# LED_Test.net
KiCad netlist of a schematic drawn in EAGLE
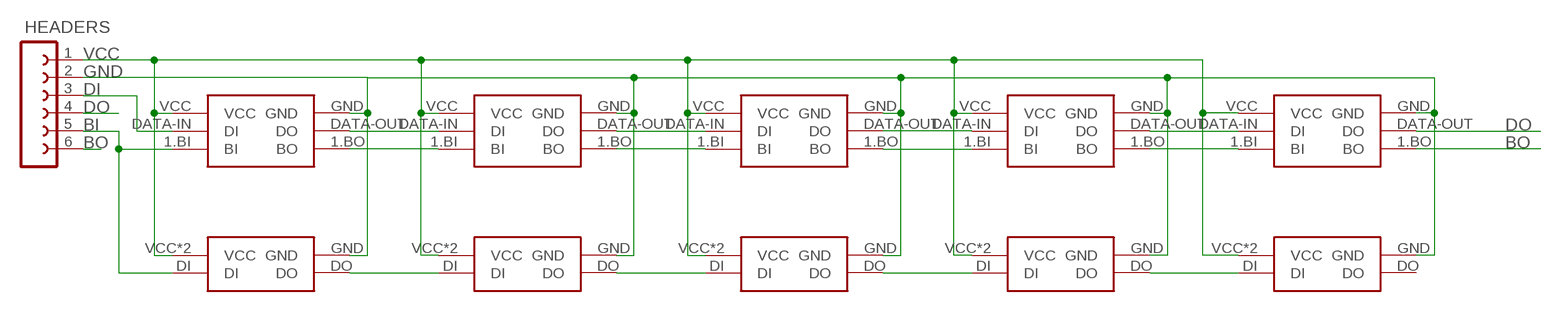
[diagram p0: schematic, sheet 1]

(export (version "E")
  (design (tool "Eeschema 10.0.6"))
  (components
    (comp (ref "HEADERS")
      (value "FE06-1")
      (footprint "eagle-import:FE06")
      (libsource (lib "eagle-import") (part "FE06-1"))
    )
    (comp (ref "U$1")
      (value "OPTO-PIXEL.COMBINEDCOMBINED-V1.04")
      (footprint "eagle-import:COMBINED4")
      (libsource (lib "eagle-import") (part "OPTO-PIXEL.COMBINEDCOMBINED-V1.04"))
    )
    (comp (ref "U$2")
      (value "OPTO-PIXEL.COMBINEDCOMBINED-V1.04")
      (footprint "eagle-import:COMBINED4")
      (libsource (lib "eagle-import") (part "OPTO-PIXEL.COMBINEDCOMBINED-V1.04"))
    )
    (comp (ref "U$3")
      (value "OPTO-PIXEL.COMBINEDCOMBINED-V1.04")
      (footprint "eagle-import:COMBINED4")
      (libsource (lib "eagle-import") (part "OPTO-PIXEL.COMBINEDCOMBINED-V1.04"))
    )
    (comp (ref "U$4")
      (value "OPTO-PIXEL.COMBINEDCOMBINED-V1.04")
      (footprint "eagle-import:COMBINED4")
      (libsource (lib "eagle-import") (part "OPTO-PIXEL.COMBINEDCOMBINED-V1.04"))
    )
    (comp (ref "U$5")
      (value "OPTO-PIXEL.COMBINEDCOMBINED-V1.04")
      (footprint "eagle-import:COMBINED4")
      (libsource (lib "eagle-import") (part "OPTO-PIXEL.COMBINEDCOMBINED-V1.04"))
    )
    (comp (ref "U$6")
      (value "OPTO-PIXEL.IN-PI55TBTPRPGPBIN-PI55TBTPRPGPB")
      (footprint "eagle-import:IN-PI55TBTPRPGPB")
      (libsource (lib "eagle-import") (part "OPTO-PIXEL.IN-PI55TBTPRPGPBIN-PI55TBTPRPGPB"))
    )
    (comp (ref "U$7")
      (value "OPTO-PIXEL.IN-PI55TBTPRPGPBIN-PI55TBTPRPGPB")
      (footprint "eagle-import:IN-PI55TBTPRPGPB")
      (libsource (lib "eagle-import") (part "OPTO-PIXEL.IN-PI55TBTPRPGPBIN-PI55TBTPRPGPB"))
    )
    (comp (ref "U$8")
      (value "OPTO-PIXEL.IN-PI55TBTPRPGPBIN-PI55TBTPRPGPB")
      (footprint "eagle-import:IN-PI55TBTPRPGPB")
      (libsource (lib "eagle-import") (part "OPTO-PIXEL.IN-PI55TBTPRPGPBIN-PI55TBTPRPGPB"))
    )
    (comp (ref "U$9")
      (value "OPTO-PIXEL.IN-PI55TBTPRPGPBIN-PI55TBTPRPGPB")
      (footprint "eagle-import:IN-PI55TBTPRPGPB")
      (libsource (lib "eagle-import") (part "OPTO-PIXEL.IN-PI55TBTPRPGPBIN-PI55TBTPRPGPB"))
    )
    (comp (ref "U$10")
      (value "OPTO-PIXEL.IN-PI55TBTPRPGPBIN-PI55TBTPRPGPB")
      (footprint "eagle-import:IN-PI55TBTPRPGPB")
      (libsource (lib "eagle-import") (part "OPTO-PIXEL.IN-PI55TBTPRPGPBIN-PI55TBTPRPGPB"))
    )
  )
  (nets
    (net (code "1") (name "/BI") (class "Default")
      (node (ref "HEADERS") (pin "5") (pinfunction "5_5") (pintype "passive"))
      (node (ref "U$1") (pin "1.BI") (pinfunction "BI_1.BI") (pintype "bidirectional"))
      (node (ref "U$6") (pin "DI") (pinfunction "DI_DI") (pintype "bidirectional"))
    )
    (net (code "2") (name "/BO") (class "Default")
      (node (ref "HEADERS") (pin "6") (pinfunction "6_6") (pintype "passive"))
      (node (ref "U$5") (pin "1.BO") (pinfunction "BO_1.BO") (pintype "bidirectional"))
    )
    (net (code "3") (name "/DI") (class "Default")
      (node (ref "HEADERS") (pin "3") (pinfunction "3_3") (pintype "passive"))
      (node (ref "U$1") (pin "DATA-IN") (pinfunction "DI_DATA-IN") (pintype "bidirectional"))
    )
    (net (code "4") (name "/DO") (class "Default")
      (node (ref "HEADERS") (pin "4") (pinfunction "4_4") (pintype "passive"))
      (node (ref "U$5") (pin "DATA-OUT") (pinfunction "DO_DATA-OUT") (pintype "bidirectional"))
    )
    (net (code "5") (name "/GND") (class "Default")
      (node (ref "HEADERS") (pin "2") (pinfunction "2_2") (pintype "passive"))
      (node (ref "U$1") (pin "GND") (pinfunction "GND_GND") (pintype "bidirectional"))
      (node (ref "U$10") (pin "GND") (pinfunction "GND_GND") (pintype "bidirectional"))
      (node (ref "U$2") (pin "GND") (pinfunction "GND_GND") (pintype "bidirectional"))
      (node (ref "U$3") (pin "GND") (pinfunction "GND_GND") (pintype "bidirectional"))
      (node (ref "U$4") (pin "GND") (pinfunction "GND_GND") (pintype "bidirectional"))
      (node (ref "U$5") (pin "GND") (pinfunction "GND_GND") (pintype "bidirectional"))
      (node (ref "U$6") (pin "GND") (pinfunction "GND_GND") (pintype "bidirectional"))
      (node (ref "U$7") (pin "GND") (pinfunction "GND_GND") (pintype "bidirectional"))
      (node (ref "U$8") (pin "GND") (pinfunction "GND_GND") (pintype "bidirectional"))
      (node (ref "U$9") (pin "GND") (pinfunction "GND_GND") (pintype "bidirectional"))
    )
    (net (code "6") (name "/VCC") (class "Default")
      (node (ref "HEADERS") (pin "1") (pinfunction "1_1") (pintype "passive"))
      (node (ref "U$1") (pin "VCC") (pinfunction "VCC_VCC") (pintype "bidirectional"))
      (node (ref "U$10") (pin "VCC") (pinfunction "VCC_VCC") (pintype "bidirectional"))
      (node (ref "U$10") (pin "VDD") (pinfunction "VCC_VDD") (pintype "bidirectional"))
      (node (ref "U$2") (pin "VCC") (pinfunction "VCC_VCC") (pintype "bidirectional"))
      (node (ref "U$3") (pin "VCC") (pinfunction "VCC_VCC") (pintype "bidirectional"))
      (node (ref "U$4") (pin "VCC") (pinfunction "VCC_VCC") (pintype "bidirectional"))
      (node (ref "U$5") (pin "VCC") (pinfunction "VCC_VCC") (pintype "bidirectional"))
      (node (ref "U$6") (pin "VCC") (pinfunction "VCC_VCC") (pintype "bidirectional"))
      (node (ref "U$6") (pin "VDD") (pinfunction "VCC_VDD") (pintype "bidirectional"))
      (node (ref "U$7") (pin "VCC") (pinfunction "VCC_VCC") (pintype "bidirectional"))
      (node (ref "U$7") (pin "VDD") (pinfunction "VCC_VDD") (pintype "bidirectional"))
      (node (ref "U$8") (pin "VCC") (pinfunction "VCC_VCC") (pintype "bidirectional"))
      (node (ref "U$8") (pin "VDD") (pinfunction "VCC_VDD") (pintype "bidirectional"))
      (node (ref "U$9") (pin "VCC") (pinfunction "VCC_VCC") (pintype "bidirectional"))
      (node (ref "U$9") (pin "VDD") (pinfunction "VCC_VDD") (pintype "bidirectional"))
    )
    (net (code "7") (name "Net-(U$1-BO)") (class "Default")
      (node (ref "U$1") (pin "1.BO") (pinfunction "BO_1.BO") (pintype "bidirectional"))
      (node (ref "U$2") (pin "1.BI") (pinfunction "BI_1.BI") (pintype "bidirectional"))
    )
    (net (code "8") (name "Net-(U$1-DO)") (class "Default")
      (node (ref "U$1") (pin "DATA-OUT") (pinfunction "DO_DATA-OUT") (pintype "bidirectional"))
      (node (ref "U$2") (pin "DATA-IN") (pinfunction "DI_DATA-IN") (pintype "bidirectional"))
    )
    (net (code "9") (name "Net-(U$2-BO)") (class "Default")
      (node (ref "U$2") (pin "1.BO") (pinfunction "BO_1.BO") (pintype "bidirectional"))
      (node (ref "U$3") (pin "1.BI") (pinfunction "BI_1.BI") (pintype "bidirectional"))
    )
    (net (code "10") (name "Net-(U$2-DO)") (class "Default")
      (node (ref "U$2") (pin "DATA-OUT") (pinfunction "DO_DATA-OUT") (pintype "bidirectional"))
      (node (ref "U$3") (pin "DATA-IN") (pinfunction "DI_DATA-IN") (pintype "bidirectional"))
    )
    (net (code "11") (name "Net-(U$3-BO)") (class "Default")
      (node (ref "U$3") (pin "1.BO") (pinfunction "BO_1.BO") (pintype "bidirectional"))
      (node (ref "U$4") (pin "1.BI") (pinfunction "BI_1.BI") (pintype "bidirectional"))
    )
    (net (code "12") (name "Net-(U$3-DO)") (class "Default")
      (node (ref "U$3") (pin "DATA-OUT") (pinfunction "DO_DATA-OUT") (pintype "bidirectional"))
      (node (ref "U$4") (pin "DATA-IN") (pinfunction "DI_DATA-IN") (pintype "bidirectional"))
    )
    (net (code "13") (name "Net-(U$4-BO)") (class "Default")
      (node (ref "U$4") (pin "1.BO") (pinfunction "BO_1.BO") (pintype "bidirectional"))
      (node (ref "U$5") (pin "1.BI") (pinfunction "BI_1.BI") (pintype "bidirectional"))
    )
    (net (code "14") (name "Net-(U$4-DO)") (class "Default")
      (node (ref "U$4") (pin "DATA-OUT") (pinfunction "DO_DATA-OUT") (pintype "bidirectional"))
      (node (ref "U$5") (pin "DATA-IN") (pinfunction "DI_DATA-IN") (pintype "bidirectional"))
    )
    (net (code "15") (name "Net-(U$6-PadDO)") (class "Default")
      (node (ref "U$6") (pin "DO") (pinfunction "DO_DO") (pintype "bidirectional"))
      (node (ref "U$7") (pin "DI") (pinfunction "DI_DI") (pintype "bidirectional"))
    )
    (net (code "16") (name "Net-(U$7-PadDO)") (class "Default")
      (node (ref "U$7") (pin "DO") (pinfunction "DO_DO") (pintype "bidirectional"))
      (node (ref "U$8") (pin "DI") (pinfunction "DI_DI") (pintype "bidirectional"))
    )
    (net (code "17") (name "Net-(U$8-PadDO)") (class "Default")
      (node (ref "U$8") (pin "DO") (pinfunction "DO_DO") (pintype "bidirectional"))
      (node (ref "U$9") (pin "DI") (pinfunction "DI_DI") (pintype "bidirectional"))
    )
    (net (code "18") (name "Net-(U$10-PadDI)") (class "Default")
      (node (ref "U$10") (pin "DI") (pinfunction "DI_DI") (pintype "bidirectional"))
      (node (ref "U$9") (pin "DO") (pinfunction "DO_DO") (pintype "bidirectional"))
    )
    (net (code "19") (name "unconnected-(U$10-PadDO)") (class "Default")
      (node (ref "U$10") (pin "DO") (pinfunction "DO_DO") (pintype "bidirectional"))
    )
  )
)
